# Misc.net
KiCad netlist of a schematic drawn in Altium Designer
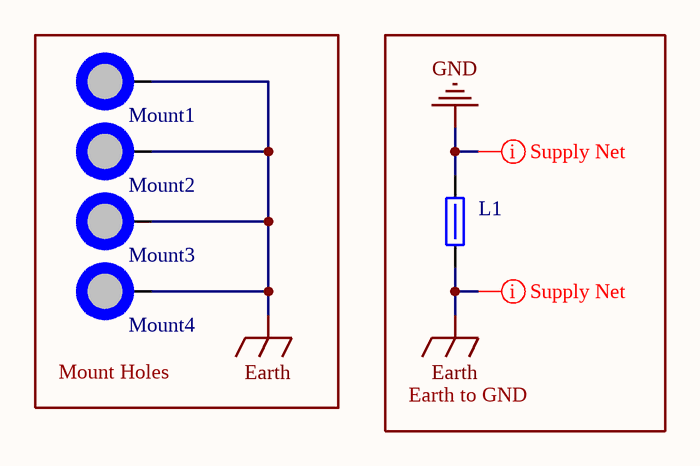
[diagram p0: Misc.SchDoc]

(export (version "E")
  (design (tool "Eeschema 10.0.6"))
  (components
    (comp (ref "L1")
      (value "742792040")
      (footprint "[Ferrite] SMD Bead 0805 (2)")
      (libsource (lib "RADM Components") (part "[Ferrite] SMD Ferrite Bead (2)"))
    )
    (comp (ref "Mount1")
      (value "M3 Mount Hole")
      (footprint "[Mount] M3 Mount Hole")
      (description "Place at least 4.5mm from board edge. Plated.")
      (libsource (lib "RADM Connectors") (part "[Mount] M3 Mount Hole"))
    )
    (comp (ref "Mount2")
      (value "M3 Mount Hole")
      (footprint "[Mount] M3 Mount Hole")
      (description "Place at least 4.5mm from board edge. Plated.")
      (libsource (lib "RADM Connectors") (part "[Mount] M3 Mount Hole"))
    )
    (comp (ref "Mount3")
      (value "M3 Mount Hole")
      (footprint "[Mount] M3 Mount Hole")
      (description "Place at least 4.5mm from board edge. Plated.")
      (libsource (lib "RADM Connectors") (part "[Mount] M3 Mount Hole"))
    )
    (comp (ref "Mount4")
      (value "M3 Mount Hole")
      (footprint "[Mount] M3 Mount Hole")
      (description "Place at least 4.5mm from board edge. Plated.")
      (libsource (lib "RADM Connectors") (part "[Mount] M3 Mount Hole"))
    )
  )
  (nets
    (net (code "1") (name "Earth") (class "Default")
      (node (ref "L1") (pin "1") (pinfunction "1_1") (pintype "passive"))
      (node (ref "Mount1") (pin "1") (pintype "power_in"))
      (node (ref "Mount2") (pin "1") (pintype "power_in"))
      (node (ref "Mount3") (pin "1") (pintype "power_in"))
      (node (ref "Mount4") (pin "1") (pintype "power_in"))
    )
    (net (code "2") (name "GND") (class "Default")
      (node (ref "L1") (pin "2") (pinfunction "2_2") (pintype "passive"))
    )
  )
)
